# 02-USER_IO.net
KiCad netlist of a schematic drawn in Altium Designer
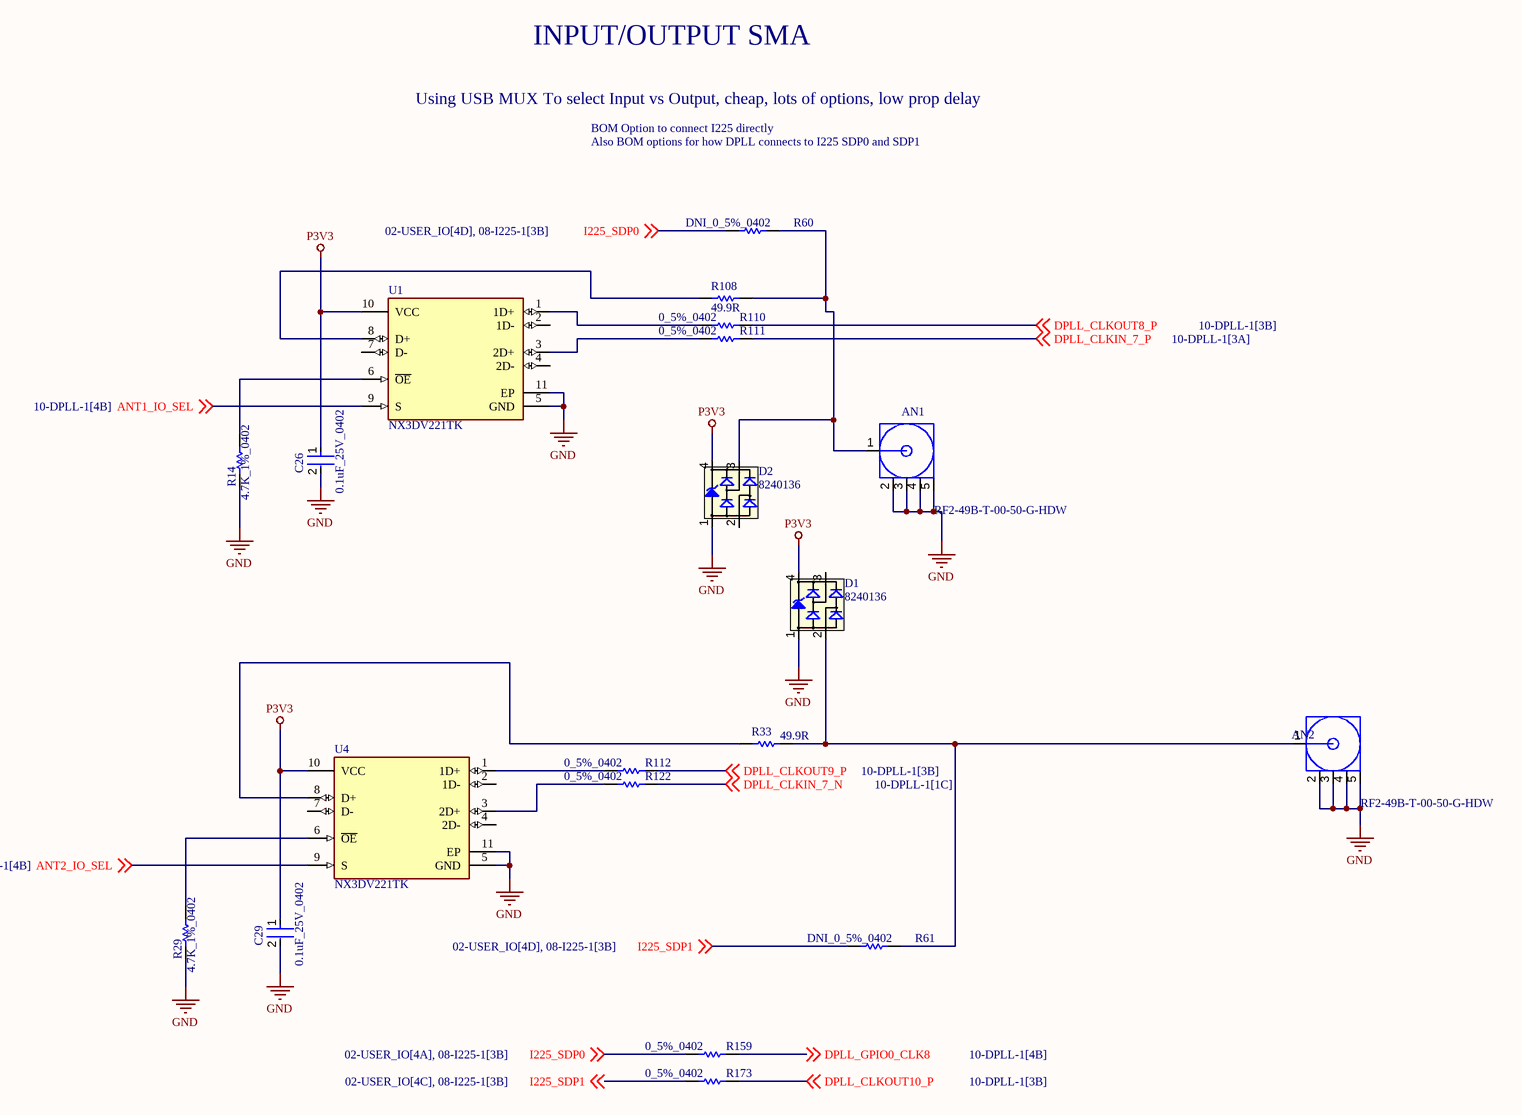
[diagram p0: 02-USER_IO.SchDoc]

(export (version "E")
  (design (tool "Eeschema 10.0.6"))
  (components
    (comp (ref "AN1")
      (value "RF2-49B-T-00-50-G-HDW")
      (footprint "SamacSys:RF249BT0050GHDW")
      (description "Connector")
      (libsource (lib "SamacSys") (part "RF2-49B-T-00-50-G-HDW"))
    )
    (comp (ref "AN2")
      (value "RF2-49B-T-00-50-G-HDW")
      (footprint "SamacSys:RF249BT0050GHDW")
      (description "Connector")
      (libsource (lib "SamacSys") (part "RF2-49B-T-00-50-G-HDW"))
    )
    (comp (ref "C26")
      (value "0.1uF_25V_0402")
      (footprint "FP-0402-L_1_0_1-W_0_5_0_1-IPC_C")
      (description "General Purpose Ceramic Capacitor, 0402, 100nF, 10%, X7R, 15%, 25V")
      (fields (field (name "VOLTAGE") "25V") (field (name "TOLERANCE") "10%"))
      (libsource (lib "Altium Content Vault") (part "b4654b650e69147ec39a6b967a45e02"))
    )
    (comp (ref "C29")
      (value "0.1uF_25V_0402")
      (footprint "FP-0402-L_1_0_1-W_0_5_0_1-IPC_C")
      (description "General Purpose Ceramic Capacitor, 0402, 100nF, 10%, X7R, 15%, 25V")
      (fields (field (name "VOLTAGE") "25V") (field (name "TOLERANCE") "10%"))
      (libsource (lib "Altium Content Vault") (part "b4654b650e69147ec39a6b967a45e02"))
    )
    (comp (ref "D1")
      (value "8240136")
      (footprint "SOT143-4L")
      (description "TVS Diode WE-TVS-HS, VRWM=3.3V")
      (fields (field (name "MANUFACTURER") "Wuerth Elektronik"))
      (libsource (lib "Altium Content Vault") (part "WE-TVS-HS-4"))
    )
    (comp (ref "D2")
      (value "8240136")
      (footprint "SOT143-4L")
      (description "TVS Diode WE-TVS-HS, VRWM=3.3V")
      (fields (field (name "MANUFACTURER") "Wuerth Elektronik"))
      (libsource (lib "Altium Content Vault") (part "WE-TVS-HS-4"))
    )
    (comp (ref "R14")
      (value "4.7K_1%_0402")
      (footprint "RESC1005X40X25NL10T10")
      (fields (field (name "MANUFACTURER") "Bourns") (field (name "PART NUMBER") "CR0402-FX-4701GLF"))
      (libsource (lib "Altium Content Vault") (part "RES"))
    )
    (comp (ref "R29")
      (value "4.7K_1%_0402")
      (footprint "RESC1005X40X25NL10T10")
      (fields (field (name "MANUFACTURER") "Bourns") (field (name "PART NUMBER") "CR0402-FX-4701GLF"))
      (libsource (lib "Altium Content Vault") (part "RES"))
    )
    (comp (ref "R33")
      (value "49.9R")
      (footprint "RESC1608X55X25NL10T15")
      (libsource (lib "Altium Content Vault") (part "RES-2"))
    )
    (comp (ref "R60")
      (value "DNI_0_5%_0402")
      (footprint "RESC1005X40X25LL10T10")
      (fields (field (name "MANUFACTURER") "KOA Speer") (field (name "PART NUMBER") "RK73Z1ETTP"))
      (libsource (lib "Altium Content Vault") (part "RES"))
    )
    (comp (ref "R61")
      (value "DNI_0_5%_0402")
      (footprint "RESC1005X40X25LL10T10")
      (fields (field (name "MANUFACTURER") "KOA Speer") (field (name "PART NUMBER") "RK73Z1ETTP"))
      (libsource (lib "Altium Content Vault") (part "RES"))
    )
    (comp (ref "R108")
      (value "49.9R")
      (footprint "RESC1608X55X25NL10T15")
      (libsource (lib "Altium Content Vault") (part "RES-2"))
    )
    (comp (ref "R110")
      (value "0_5%_0402")
      (footprint "RESC1005X40X25LL10T10")
      (fields (field (name "MANUFACTURER") "KOA Speer") (field (name "PART NUMBER") "RK73Z1ETTP"))
      (libsource (lib "Altium Content Vault") (part "RES"))
    )
    (comp (ref "R111")
      (value "0_5%_0402")
      (footprint "RESC1005X40X25LL10T10")
      (fields (field (name "MANUFACTURER") "KOA Speer") (field (name "PART NUMBER") "RK73Z1ETTP"))
      (libsource (lib "Altium Content Vault") (part "RES"))
    )
    (comp (ref "R112")
      (value "0_5%_0402")
      (footprint "RESC1005X40X25LL10T10")
      (fields (field (name "MANUFACTURER") "KOA Speer") (field (name "PART NUMBER") "RK73Z1ETTP"))
      (libsource (lib "Altium Content Vault") (part "RES"))
    )
    (comp (ref "R122")
      (value "0_5%_0402")
      (footprint "RESC1005X40X25LL10T10")
      (fields (field (name "MANUFACTURER") "KOA Speer") (field (name "PART NUMBER") "RK73Z1ETTP"))
      (libsource (lib "Altium Content Vault") (part "RES"))
    )
    (comp (ref "R159")
      (value "0_5%_0402")
      (footprint "RESC1005X40X25LL10T10")
      (fields (field (name "MANUFACTURER") "KOA Speer") (field (name "PART NUMBER") "RK73Z1ETTP"))
      (libsource (lib "Altium Content Vault") (part "RES"))
    )
    (comp (ref "R173")
      (value "0_5%_0402")
      (footprint "RESC1005X40X25LL10T10")
      (fields (field (name "MANUFACTURER") "KOA Speer") (field (name "PART NUMBER") "RK73Z1ETTP"))
      (libsource (lib "Altium Content Vault") (part "RES"))
    )
    (comp (ref "U1")
      (value "NX3DV221TK")
      (footprint "FP-SOT650-2-MFG")
      (description "USB Switch IC 1 Channel 10-HVSON (3x3)")
      (libsource (lib "Altium Content Vault") (part "bce77ec48a709d17f0bdc2c26d779bf"))
    )
    (comp (ref "U4")
      (value "NX3DV221TK")
      (footprint "FP-SOT650-2-MFG")
      (description "USB Switch IC 1 Channel 10-HVSON (3x3)")
      (libsource (lib "Altium Content Vault") (part "bce77ec48a709d17f0bdc2c26d779bf"))
    )
  )
  (nets
    (net (code "1") (name "ANT1_IO_SEL") (class "Default")
      (node (ref "U1") (pin "9") (pinfunction "S_9") (pintype "input"))
    )
    (net (code "2") (name "ANT2_IO_SEL") (class "Default")
      (node (ref "U4") (pin "9") (pinfunction "S_9") (pintype "input"))
    )
    (net (code "3") (name "DPLL_CLKIN_7_N") (class "Default")
      (node (ref "R122") (pin "2") (pinfunction "2_2") (pintype "passive"))
    )
    (net (code "4") (name "DPLL_CLKIN_7_P") (class "Default")
      (node (ref "R111") (pin "2") (pinfunction "2_2") (pintype "passive"))
    )
    (net (code "5") (name "DPLL_CLKOUT8_P") (class "Default")
      (node (ref "R110") (pin "2") (pinfunction "2_2") (pintype "passive"))
    )
    (net (code "6") (name "DPLL_CLKOUT9_P") (class "Default")
      (node (ref "R112") (pin "2") (pinfunction "2_2") (pintype "passive"))
    )
    (net (code "7") (name "DPLL_CLKOUT10_P") (class "Default")
      (node (ref "R173") (pin "2") (pinfunction "2_2") (pintype "passive"))
    )
    (net (code "8") (name "DPLL_GPIO0_CLK8") (class "Default")
      (node (ref "R159") (pin "2") (pinfunction "2_2") (pintype "passive"))
    )
    (net (code "9") (name "GND") (class "Default")
      (node (ref "AN1") (pin "2") (pinfunction "2_2") (pintype "passive"))
      (node (ref "AN1") (pin "3") (pinfunction "3_3") (pintype "passive"))
      (node (ref "AN1") (pin "4") (pinfunction "4_4") (pintype "passive"))
      (node (ref "AN1") (pin "5") (pinfunction "5_5") (pintype "passive"))
      (node (ref "AN2") (pin "2") (pinfunction "2_2") (pintype "passive"))
      (node (ref "AN2") (pin "3") (pinfunction "3_3") (pintype "passive"))
      (node (ref "AN2") (pin "4") (pinfunction "4_4") (pintype "passive"))
      (node (ref "AN2") (pin "5") (pinfunction "5_5") (pintype "passive"))
      (node (ref "C26") (pin "2") (pinfunction "2_2") (pintype "passive"))
      (node (ref "C29") (pin "2") (pinfunction "2_2") (pintype "passive"))
      (node (ref "D1") (pin "1") (pinfunction "GND_1") (pintype "passive"))
      (node (ref "D2") (pin "1") (pinfunction "GND_1") (pintype "passive"))
      (node (ref "R14") (pin "2") (pinfunction "2_2") (pintype "passive"))
      (node (ref "R29") (pin "2") (pinfunction "2_2") (pintype "passive"))
      (node (ref "U1") (pin "11") (pinfunction "EP_11") (pintype "passive"))
      (node (ref "U1") (pin "5") (pinfunction "GND_5") (pintype "power_in"))
      (node (ref "U4") (pin "11") (pinfunction "EP_11") (pintype "passive"))
      (node (ref "U4") (pin "5") (pinfunction "GND_5") (pintype "power_in"))
    )
    (net (code "10") (name "I225_SDP0") (class "Default")
      (node (ref "R159") (pin "1") (pinfunction "1_1") (pintype "passive"))
      (node (ref "R60") (pin "1") (pinfunction "1_1") (pintype "passive"))
    )
    (net (code "11") (name "I225_SDP1") (class "Default")
      (node (ref "R173") (pin "1") (pinfunction "1_1") (pintype "passive"))
      (node (ref "R61") (pin "1") (pinfunction "1_1") (pintype "passive"))
    )
    (net (code "12") (name "Net-(D1-I{slash}O1)") (class "Default")
      (node (ref "AN2") (pin "1") (pinfunction "1_1") (pintype "passive"))
      (node (ref "D1") (pin "2") (pinfunction "I/O1_2") (pintype "passive"))
      (node (ref "R33") (pin "2") (pinfunction "2_2") (pintype "passive"))
      (node (ref "R61") (pin "2") (pinfunction "2_2") (pintype "passive"))
    )
    (net (code "13") (name "Net-(D2-I{slash}O2)") (class "Default")
      (node (ref "AN1") (pin "1") (pinfunction "1_1") (pintype "passive"))
      (node (ref "D2") (pin "3") (pinfunction "I/O2_3") (pintype "passive"))
      (node (ref "R108") (pin "1") (pinfunction "1_1") (pintype "passive"))
      (node (ref "R60") (pin "2") (pinfunction "2_2") (pintype "passive"))
    )
    (net (code "14") (name "Net-(U1-1D+)") (class "Default")
      (node (ref "R110") (pin "1") (pinfunction "1_1") (pintype "passive"))
      (node (ref "U1") (pin "1") (pinfunction "1D+_1") (pintype "bidirectional"))
    )
    (net (code "15") (name "Net-(U1-2D+)") (class "Default")
      (node (ref "R111") (pin "1") (pinfunction "1_1") (pintype "passive"))
      (node (ref "U1") (pin "3") (pinfunction "2D+_3") (pintype "bidirectional"))
    )
    (net (code "16") (name "Net-(U1-D+)") (class "Default")
      (node (ref "R108") (pin "2") (pinfunction "2_2") (pintype "passive"))
      (node (ref "U1") (pin "8") (pinfunction "D+_8") (pintype "bidirectional"))
    )
    (net (code "17") (name "Net-(U1-~{OE})") (class "Default")
      (node (ref "R14") (pin "1") (pinfunction "1_1") (pintype "passive"))
      (node (ref "U1") (pin "6") (pinfunction "~{OE}_6") (pintype "input"))
    )
    (net (code "18") (name "Net-(U4-1D+)") (class "Default")
      (node (ref "R112") (pin "1") (pinfunction "1_1") (pintype "passive"))
      (node (ref "U4") (pin "1") (pinfunction "1D+_1") (pintype "bidirectional"))
    )
    (net (code "19") (name "Net-(U4-2D+)") (class "Default")
      (node (ref "R122") (pin "1") (pinfunction "1_1") (pintype "passive"))
      (node (ref "U4") (pin "3") (pinfunction "2D+_3") (pintype "bidirectional"))
    )
    (net (code "20") (name "Net-(U4-D+)") (class "Default")
      (node (ref "R33") (pin "1") (pinfunction "1_1") (pintype "passive"))
      (node (ref "U4") (pin "8") (pinfunction "D+_8") (pintype "bidirectional"))
    )
    (net (code "21") (name "Net-(U4-~{OE})") (class "Default")
      (node (ref "R29") (pin "1") (pinfunction "1_1") (pintype "passive"))
      (node (ref "U4") (pin "6") (pinfunction "~{OE}_6") (pintype "input"))
    )
    (net (code "22") (name "P3V3") (class "Default")
      (node (ref "C26") (pin "1") (pinfunction "1_1") (pintype "passive"))
      (node (ref "C29") (pin "1") (pinfunction "1_1") (pintype "passive"))
      (node (ref "D1") (pin "4") (pinfunction "VDD_4") (pintype "passive"))
      (node (ref "D2") (pin "4") (pinfunction "VDD_4") (pintype "passive"))
      (node (ref "U1") (pin "10") (pinfunction "VCC_10") (pintype "power_in"))
      (node (ref "U4") (pin "10") (pinfunction "VCC_10") (pintype "power_in"))
    )
    (net (code "23") (name "unconnected-(D1-I{slash}O2-Pad3)") (class "Default")
      (node (ref "D1") (pin "3") (pinfunction "I/O2_3") (pintype "passive"))
    )
    (net (code "24") (name "unconnected-(D2-I{slash}O1-Pad2)") (class "Default")
      (node (ref "D2") (pin "2") (pinfunction "I/O1_2") (pintype "passive"))
    )
    (net (code "25") (name "unconnected-(U1-1D--Pad2)") (class "Default")
      (node (ref "U1") (pin "2") (pinfunction "1D-_2") (pintype "bidirectional"))
    )
    (net (code "26") (name "unconnected-(U1-2D--Pad4)") (class "Default")
      (node (ref "U1") (pin "4") (pinfunction "2D-_4") (pintype "bidirectional"))
    )
    (net (code "27") (name "unconnected-(U1-D--Pad7)") (class "Default")
      (node (ref "U1") (pin "7") (pinfunction "D-_7") (pintype "bidirectional"))
    )
    (net (code "28") (name "unconnected-(U4-1D--Pad2)") (class "Default")
      (node (ref "U4") (pin "2") (pinfunction "1D-_2") (pintype "bidirectional"))
    )
    (net (code "29") (name "unconnected-(U4-2D--Pad4)") (class "Default")
      (node (ref "U4") (pin "4") (pinfunction "2D-_4") (pintype "bidirectional"))
    )
    (net (code "30") (name "unconnected-(U4-D--Pad7)") (class "Default")
      (node (ref "U4") (pin "7") (pinfunction "D-_7") (pintype "bidirectional"))
    )
  )
)
